# ledSkateBoard.net
KiCad netlist of a schematic drawn in EAGLE
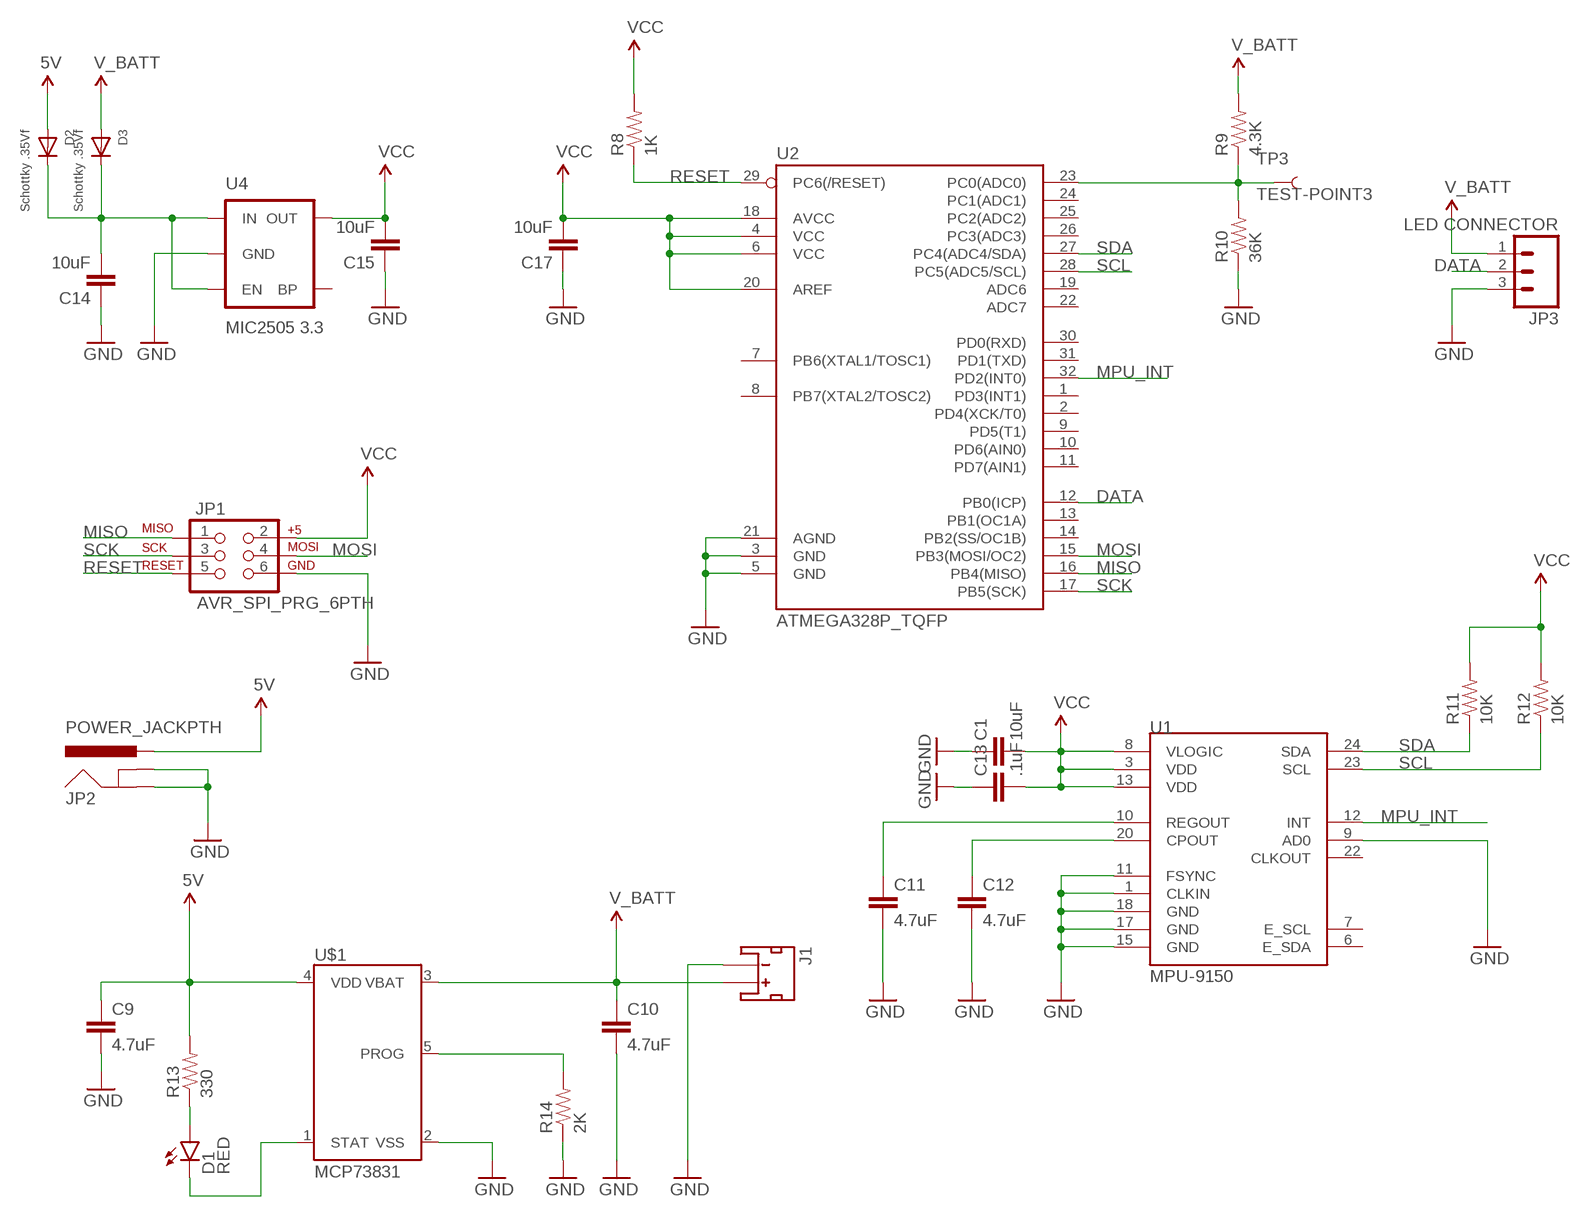
[diagram p0: schematic, sheet 1]

(export (version "E")
  (design (tool "Eeschema 10.0.6"))
  (components
    (comp (ref "C1")
      (value "10uF")
      (footprint "eagle-import:0805")
      (libsource (lib "eagle-import") (part "CAP0805"))
    )
    (comp (ref "C9")
      (value "4.7uF")
      (footprint "eagle-import:0805")
      (libsource (lib "eagle-import") (part "CAP0805"))
    )
    (comp (ref "C10")
      (value "4.7uF")
      (footprint "eagle-import:0805")
      (libsource (lib "eagle-import") (part "CAP0805"))
    )
    (comp (ref "C11")
      (value "4.7uF")
      (footprint "eagle-import:0805")
      (libsource (lib "eagle-import") (part "CAP0805"))
    )
    (comp (ref "C12")
      (value "4.7uF")
      (footprint "eagle-import:0805")
      (libsource (lib "eagle-import") (part "CAP0805"))
    )
    (comp (ref "C13")
      (value ".1uF")
      (footprint "eagle-import:0805")
      (libsource (lib "eagle-import") (part "CAP0805"))
    )
    (comp (ref "C14")
      (value "10uF")
      (footprint "eagle-import:0805")
      (libsource (lib "eagle-import") (part "CAP0805"))
    )
    (comp (ref "C15")
      (value "10uF")
      (footprint "eagle-import:0805")
      (libsource (lib "eagle-import") (part "CAP0805"))
    )
    (comp (ref "C17")
      (value "10uF")
      (footprint "eagle-import:0805")
      (libsource (lib "eagle-import") (part "CAP0805"))
    )
    (comp (ref "D1")
      (value "RED")
      (footprint "eagle-import:LED-0603")
      (libsource (lib "eagle-import") (part "LED-RED0603"))
    )
    (comp (ref "D2")
      (value "Schottky .35Vf")
      (footprint "eagle-import:SMADIODE")
      (libsource (lib "eagle-import") (part "DIODESMA"))
    )
    (comp (ref "D3")
      (value "Schottky .35Vf")
      (footprint "eagle-import:SMADIODE")
      (libsource (lib "eagle-import") (part "DIODESMA"))
    )
    (comp (ref "J1")
      (value "JST")
      (footprint "eagle-import:JST-2-SMD")
      (libsource (lib "eagle-import") (part "JST_2MM_MALE"))
    )
    (comp (ref "JP1")
      (value "AVR_SPI_PRG_6PTH")
      (footprint "eagle-import:2X3")
      (libsource (lib "eagle-import") (part "AVR_SPI_PRG_6PTH"))
    )
    (comp (ref "JP2")
      (value "POWER_JACKPTH")
      (footprint "eagle-import:POWER_JACK_PTH")
      (libsource (lib "eagle-import") (part "POWER_JACKPTH"))
    )
    (comp (ref "JP3")
      (value "LED CONNECTOR")
      (footprint "eagle-import:1X03")
      (libsource (lib "eagle-import") (part "M03PTH"))
    )
    (comp (ref "R8")
      (value "1K")
      (footprint "eagle-import:0805")
      (libsource (lib "eagle-import") (part "RESISTOR0805-RES"))
    )
    (comp (ref "R9")
      (value "4.3K")
      (footprint "eagle-import:0805")
      (libsource (lib "eagle-import") (part "RESISTOR0805-RES"))
    )
    (comp (ref "R10")
      (value "36K")
      (footprint "eagle-import:0805")
      (libsource (lib "eagle-import") (part "RESISTOR0805-RES"))
    )
    (comp (ref "R11")
      (value "10K")
      (footprint "eagle-import:0805")
      (libsource (lib "eagle-import") (part "RESISTOR0805-RES"))
    )
    (comp (ref "R12")
      (value "10K")
      (footprint "eagle-import:0805")
      (libsource (lib "eagle-import") (part "RESISTOR0805-RES"))
    )
    (comp (ref "R13")
      (value "330")
      (footprint "eagle-import:0805")
      (libsource (lib "eagle-import") (part "RESISTOR0805-RES"))
    )
    (comp (ref "R14")
      (value "2K")
      (footprint "eagle-import:0805")
      (libsource (lib "eagle-import") (part "RESISTOR0805-RES"))
    )
    (comp (ref "TP3")
      (value "TEST-POINT3")
      (footprint "eagle-import:PAD.03X.03")
      (libsource (lib "eagle-import") (part "TEST-POINT3"))
    )
    (comp (ref "U$1")
      (value "MCP73831")
      (footprint "eagle-import:SOT23-5")
      (libsource (lib "eagle-import") (part "MCP73831"))
    )
    (comp (ref "U1")
      (value "MPU-9150")
      (footprint "eagle-import:QFN-24-NP")
      (libsource (lib "eagle-import") (part "MPU-9150QFN-24-NP"))
    )
    (comp (ref "U2")
      (value "ATMEGA328P_TQFP")
      (footprint "eagle-import:TQFP32-08")
      (libsource (lib "eagle-import") (part "ATMEGA328P_TQFP"))
    )
    (comp (ref "U4")
      (value "MIC2505 3.3")
      (footprint "eagle-import:SOT23-5")
      (libsource (lib "eagle-import") (part "MIC52053.3V"))
    )
  )
  (nets
    (net (code "1") (name "/DATA") (class "Default")
      (node (ref "JP3") (pin "2") (pinfunction "2_2") (pintype "passive"))
      (node (ref "U2") (pin "12") (pinfunction "PB0(ICP)_12") (pintype "bidirectional"))
    )
    (net (code "2") (name "/MISO") (class "Default")
      (node (ref "JP1") (pin "1") (pinfunction "1_1") (pintype "passive"))
      (node (ref "U2") (pin "16") (pinfunction "PB4(MISO)_16") (pintype "bidirectional"))
    )
    (net (code "3") (name "/MOSI") (class "Default")
      (node (ref "JP1") (pin "4") (pinfunction "4_4") (pintype "passive"))
      (node (ref "U2") (pin "15") (pinfunction "PB3(MOSI/OC2)_15") (pintype "bidirectional"))
    )
    (net (code "4") (name "/MPU_INT") (class "Default")
      (node (ref "U1") (pin "12") (pinfunction "INT_12") (pintype "bidirectional"))
      (node (ref "U2") (pin "32") (pinfunction "PD2(INT0)_32") (pintype "bidirectional"))
    )
    (net (code "5") (name "/RESET") (class "Default")
      (node (ref "JP1") (pin "5") (pinfunction "5_5") (pintype "passive"))
      (node (ref "R8") (pin "1") (pinfunction "1_1") (pintype "passive"))
      (node (ref "U2") (pin "29") (pinfunction "PC6(/RESET)_29") (pintype "bidirectional"))
    )
    (net (code "6") (name "/SCK") (class "Default")
      (node (ref "JP1") (pin "3") (pinfunction "3_3") (pintype "passive"))
      (node (ref "U2") (pin "17") (pinfunction "PB5(SCK)_17") (pintype "bidirectional"))
    )
    (net (code "7") (name "/SCL") (class "Default")
      (node (ref "R12") (pin "1") (pinfunction "1_1") (pintype "passive"))
      (node (ref "U1") (pin "23") (pinfunction "SCL_23") (pintype "bidirectional"))
      (node (ref "U2") (pin "28") (pinfunction "PC5(ADC5/SCL)_28") (pintype "bidirectional"))
    )
    (net (code "8") (name "/SDA") (class "Default")
      (node (ref "R11") (pin "1") (pinfunction "1_1") (pintype "passive"))
      (node (ref "U1") (pin "24") (pinfunction "SDA_24") (pintype "bidirectional"))
      (node (ref "U2") (pin "27") (pinfunction "PC4(ADC4/SDA)_27") (pintype "bidirectional"))
    )
    (net (code "9") (name "5V") (class "Default")
      (node (ref "C9") (pin "1") (pinfunction "1_1") (pintype "passive"))
      (node (ref "D2") (pin "A") (pinfunction "A_A") (pintype "passive"))
      (node (ref "JP2") (pin "PWR") (pinfunction "PWR_PWR") (pintype "bidirectional"))
      (node (ref "R13") (pin "2") (pinfunction "2_2") (pintype "passive"))
      (node (ref "U$1") (pin "4") (pinfunction "VDD_4") (pintype "power_in"))
    )
    (net (code "10") (name "GND") (class "Default")
      (node (ref "C1") (pin "1") (pinfunction "1_1") (pintype "passive"))
      (node (ref "C10") (pin "2") (pinfunction "2_2") (pintype "passive"))
      (node (ref "C11") (pin "2") (pinfunction "2_2") (pintype "passive"))
      (node (ref "C12") (pin "2") (pinfunction "2_2") (pintype "passive"))
      (node (ref "C13") (pin "1") (pinfunction "1_1") (pintype "passive"))
      (node (ref "C14") (pin "1") (pinfunction "1_1") (pintype "passive"))
      (node (ref "C15") (pin "1") (pinfunction "1_1") (pintype "passive"))
      (node (ref "C17") (pin "1") (pinfunction "1_1") (pintype "passive"))
      (node (ref "C9") (pin "2") (pinfunction "2_2") (pintype "passive"))
      (node (ref "J1") (pin "1") (pinfunction "-_1") (pintype "bidirectional"))
      (node (ref "JP1") (pin "6") (pinfunction "6_6") (pintype "passive"))
      (node (ref "JP2") (pin "GND") (pinfunction "GND_GND") (pintype "bidirectional"))
      (node (ref "JP2") (pin "GNDBREAK") (pinfunction "GNDBREAK_GNDBREAK") (pintype "bidirectional"))
      (node (ref "JP3") (pin "3") (pinfunction "3_3") (pintype "passive"))
      (node (ref "R10") (pin "1") (pinfunction "1_1") (pintype "passive"))
      (node (ref "R14") (pin "1") (pinfunction "1_1") (pintype "passive"))
      (node (ref "U$1") (pin "2") (pinfunction "VSS_2") (pintype "power_in"))
      (node (ref "U1") (pin "1") (pinfunction "CLKIN_1") (pintype "bidirectional"))
      (node (ref "U1") (pin "11") (pinfunction "FSYNC_11") (pintype "bidirectional"))
      (node (ref "U1") (pin "15") (pinfunction "GND_15") (pintype "bidirectional"))
      (node (ref "U1") (pin "17") (pinfunction "GND_17") (pintype "bidirectional"))
      (node (ref "U1") (pin "18") (pinfunction "GND_18") (pintype "bidirectional"))
      (node (ref "U1") (pin "9") (pinfunction "AD0_9") (pintype "bidirectional"))
      (node (ref "U2") (pin "21") (pinfunction "AGND_21") (pintype "bidirectional"))
      (node (ref "U2") (pin "3") (pinfunction "GND_3") (pintype "bidirectional"))
      (node (ref "U2") (pin "5") (pinfunction "GND_5") (pintype "bidirectional"))
      (node (ref "U4") (pin "2") (pinfunction "GND_2") (pintype "input"))
    )
    (net (code "11") (name "Net-(D1-PadA)") (class "Default")
      (node (ref "D1") (pin "A") (pinfunction "A_A") (pintype "passive"))
      (node (ref "R13") (pin "1") (pinfunction "1_1") (pintype "passive"))
    )
    (net (code "12") (name "Net-(TP3-1)") (class "Default")
      (node (ref "R10") (pin "2") (pinfunction "2_2") (pintype "passive"))
      (node (ref "R9") (pin "1") (pinfunction "1_1") (pintype "passive"))
      (node (ref "TP3") (pin "P$1") (pinfunction "1_P$1") (pintype "bidirectional"))
      (node (ref "U2") (pin "23") (pinfunction "PC0(ADC0)_23") (pintype "bidirectional"))
    )
    (net (code "13") (name "Net-(U$1-PROG)") (class "Default")
      (node (ref "R14") (pin "2") (pinfunction "2_2") (pintype "passive"))
      (node (ref "U$1") (pin "5") (pinfunction "PROG_5") (pintype "input"))
    )
    (net (code "14") (name "Net-(U$1-STAT)") (class "Default")
      (node (ref "D1") (pin "C") (pinfunction "C_C") (pintype "passive"))
      (node (ref "U$1") (pin "1") (pinfunction "STAT_1") (pintype "output"))
    )
    (net (code "15") (name "Net-(U1-CPOUT)") (class "Default")
      (node (ref "C12") (pin "1") (pinfunction "1_1") (pintype "passive"))
      (node (ref "U1") (pin "20") (pinfunction "CPOUT_20") (pintype "bidirectional"))
    )
    (net (code "16") (name "Net-(U1-REGOUT)") (class "Default")
      (node (ref "C11") (pin "1") (pinfunction "1_1") (pintype "passive"))
      (node (ref "U1") (pin "10") (pinfunction "REGOUT_10") (pintype "bidirectional"))
    )
    (net (code "17") (name "Net-(U4-EN)") (class "Default")
      (node (ref "C14") (pin "2") (pinfunction "2_2") (pintype "passive"))
      (node (ref "D2") (pin "C") (pinfunction "C_C") (pintype "passive"))
      (node (ref "D3") (pin "C") (pinfunction "C_C") (pintype "passive"))
      (node (ref "U4") (pin "1") (pinfunction "IN_1") (pintype "input"))
      (node (ref "U4") (pin "3") (pinfunction "EN_3") (pintype "input"))
    )
    (net (code "18") (name "VCC") (class "Default")
      (node (ref "C1") (pin "2") (pinfunction "2_2") (pintype "passive"))
      (node (ref "C13") (pin "2") (pinfunction "2_2") (pintype "passive"))
      (node (ref "C15") (pin "2") (pinfunction "2_2") (pintype "passive"))
      (node (ref "C17") (pin "2") (pinfunction "2_2") (pintype "passive"))
      (node (ref "JP1") (pin "2") (pinfunction "2_2") (pintype "passive"))
      (node (ref "R11") (pin "2") (pinfunction "2_2") (pintype "passive"))
      (node (ref "R12") (pin "2") (pinfunction "2_2") (pintype "passive"))
      (node (ref "R8") (pin "2") (pinfunction "2_2") (pintype "passive"))
      (node (ref "U1") (pin "13") (pinfunction "VDD_13") (pintype "bidirectional"))
      (node (ref "U1") (pin "3") (pinfunction "VDD_3") (pintype "bidirectional"))
      (node (ref "U1") (pin "8") (pinfunction "VLOGIC_8") (pintype "bidirectional"))
      (node (ref "U2") (pin "18") (pinfunction "AVCC_18") (pintype "bidirectional"))
      (node (ref "U2") (pin "20") (pinfunction "AREF_20") (pintype "bidirectional"))
      (node (ref "U2") (pin "4") (pinfunction "VCC_4") (pintype "bidirectional"))
      (node (ref "U2") (pin "6") (pinfunction "VCC_6") (pintype "bidirectional"))
      (node (ref "U4") (pin "5") (pinfunction "OUT_5") (pintype "passive"))
    )
    (net (code "19") (name "V_BATT") (class "Default")
      (node (ref "C10") (pin "1") (pinfunction "1_1") (pintype "passive"))
      (node (ref "D3") (pin "A") (pinfunction "A_A") (pintype "passive"))
      (node (ref "J1") (pin "2") (pinfunction "+_2") (pintype "bidirectional"))
      (node (ref "JP3") (pin "1") (pinfunction "1_1") (pintype "passive"))
      (node (ref "R9") (pin "2") (pinfunction "2_2") (pintype "passive"))
      (node (ref "U$1") (pin "3") (pinfunction "VBAT_3") (pintype "power_in"))
    )
    (net (code "20") (name "unconnected-(J1-PAD1-PadNC1)") (class "Default")
      (node (ref "J1") (pin "NC1") (pinfunction "PAD1_NC1") (pintype "bidirectional"))
    )
    (net (code "21") (name "unconnected-(J1-PAD2-PadNC2)") (class "Default")
      (node (ref "J1") (pin "NC2") (pinfunction "PAD2_NC2") (pintype "bidirectional"))
    )
    (net (code "22") (name "unconnected-(U1-CLKOUT-Pad22)") (class "Default")
      (node (ref "U1") (pin "22") (pinfunction "CLKOUT_22") (pintype "bidirectional"))
    )
    (net (code "23") (name "unconnected-(U1-E_SCL-Pad7)") (class "Default")
      (node (ref "U1") (pin "7") (pinfunction "E_SCL_7") (pintype "bidirectional"))
    )
    (net (code "24") (name "unconnected-(U1-E_SDA-Pad6)") (class "Default")
      (node (ref "U1") (pin "6") (pinfunction "E_SDA_6") (pintype "bidirectional"))
    )
    (net (code "25") (name "unconnected-(U2-ADC6-Pad19)") (class "Default")
      (node (ref "U2") (pin "19") (pinfunction "ADC6_19") (pintype "bidirectional"))
    )
    (net (code "26") (name "unconnected-(U2-ADC7-Pad22)") (class "Default")
      (node (ref "U2") (pin "22") (pinfunction "ADC7_22") (pintype "bidirectional"))
    )
    (net (code "27") (name "unconnected-(U2-PB1(OC1A)-Pad13)") (class "Default")
      (node (ref "U2") (pin "13") (pinfunction "PB1(OC1A)_13") (pintype "bidirectional"))
    )
    (net (code "28") (name "unconnected-(U2-PB2(SS{slash}OC1B)-Pad14)") (class "Default")
      (node (ref "U2") (pin "14") (pinfunction "PB2(SS/OC1B)_14") (pintype "bidirectional"))
    )
    (net (code "29") (name "unconnected-(U2-PB6(XTAL1{slash}TOSC1)-Pad7)") (class "Default")
      (node (ref "U2") (pin "7") (pinfunction "PB6(XTAL1/TOSC1)_7") (pintype "bidirectional"))
    )
    (net (code "30") (name "unconnected-(U2-PB7(XTAL2{slash}TOSC2)-Pad8)") (class "Default")
      (node (ref "U2") (pin "8") (pinfunction "PB7(XTAL2/TOSC2)_8") (pintype "bidirectional"))
    )
    (net (code "31") (name "unconnected-(U2-PC1(ADC1)-Pad24)") (class "Default")
      (node (ref "U2") (pin "24") (pinfunction "PC1(ADC1)_24") (pintype "bidirectional"))
    )
    (net (code "32") (name "unconnected-(U2-PC2(ADC2)-Pad25)") (class "Default")
      (node (ref "U2") (pin "25") (pinfunction "PC2(ADC2)_25") (pintype "bidirectional"))
    )
    (net (code "33") (name "unconnected-(U2-PC3(ADC3)-Pad26)") (class "Default")
      (node (ref "U2") (pin "26") (pinfunction "PC3(ADC3)_26") (pintype "bidirectional"))
    )
    (net (code "34") (name "unconnected-(U2-PD0(RXD)-Pad30)") (class "Default")
      (node (ref "U2") (pin "30") (pinfunction "PD0(RXD)_30") (pintype "bidirectional"))
    )
    (net (code "35") (name "unconnected-(U2-PD1(TXD)-Pad31)") (class "Default")
      (node (ref "U2") (pin "31") (pinfunction "PD1(TXD)_31") (pintype "bidirectional"))
    )
    (net (code "36") (name "unconnected-(U2-PD3(INT1)-Pad1)") (class "Default")
      (node (ref "U2") (pin "1") (pinfunction "PD3(INT1)_1") (pintype "bidirectional"))
    )
    (net (code "37") (name "unconnected-(U2-PD4(XCK{slash}T0)-Pad2)") (class "Default")
      (node (ref "U2") (pin "2") (pinfunction "PD4(XCK/T0)_2") (pintype "bidirectional"))
    )
    (net (code "38") (name "unconnected-(U2-PD5(T1)-Pad9)") (class "Default")
      (node (ref "U2") (pin "9") (pinfunction "PD5(T1)_9") (pintype "bidirectional"))
    )
    (net (code "39") (name "unconnected-(U2-PD6(AIN0)-Pad10)") (class "Default")
      (node (ref "U2") (pin "10") (pinfunction "PD6(AIN0)_10") (pintype "bidirectional"))
    )
    (net (code "40") (name "unconnected-(U2-PD7(AIN1)-Pad11)") (class "Default")
      (node (ref "U2") (pin "11") (pinfunction "PD7(AIN1)_11") (pintype "bidirectional"))
    )
    (net (code "41") (name "unconnected-(U4-BP-Pad4)") (class "Default")
      (node (ref "U4") (pin "4") (pinfunction "BP_4") (pintype "input"))
    )
  )
)
